# SparkFun_ZED-F9R_v12_uFL.net
KiCad netlist of a schematic drawn in EAGLE
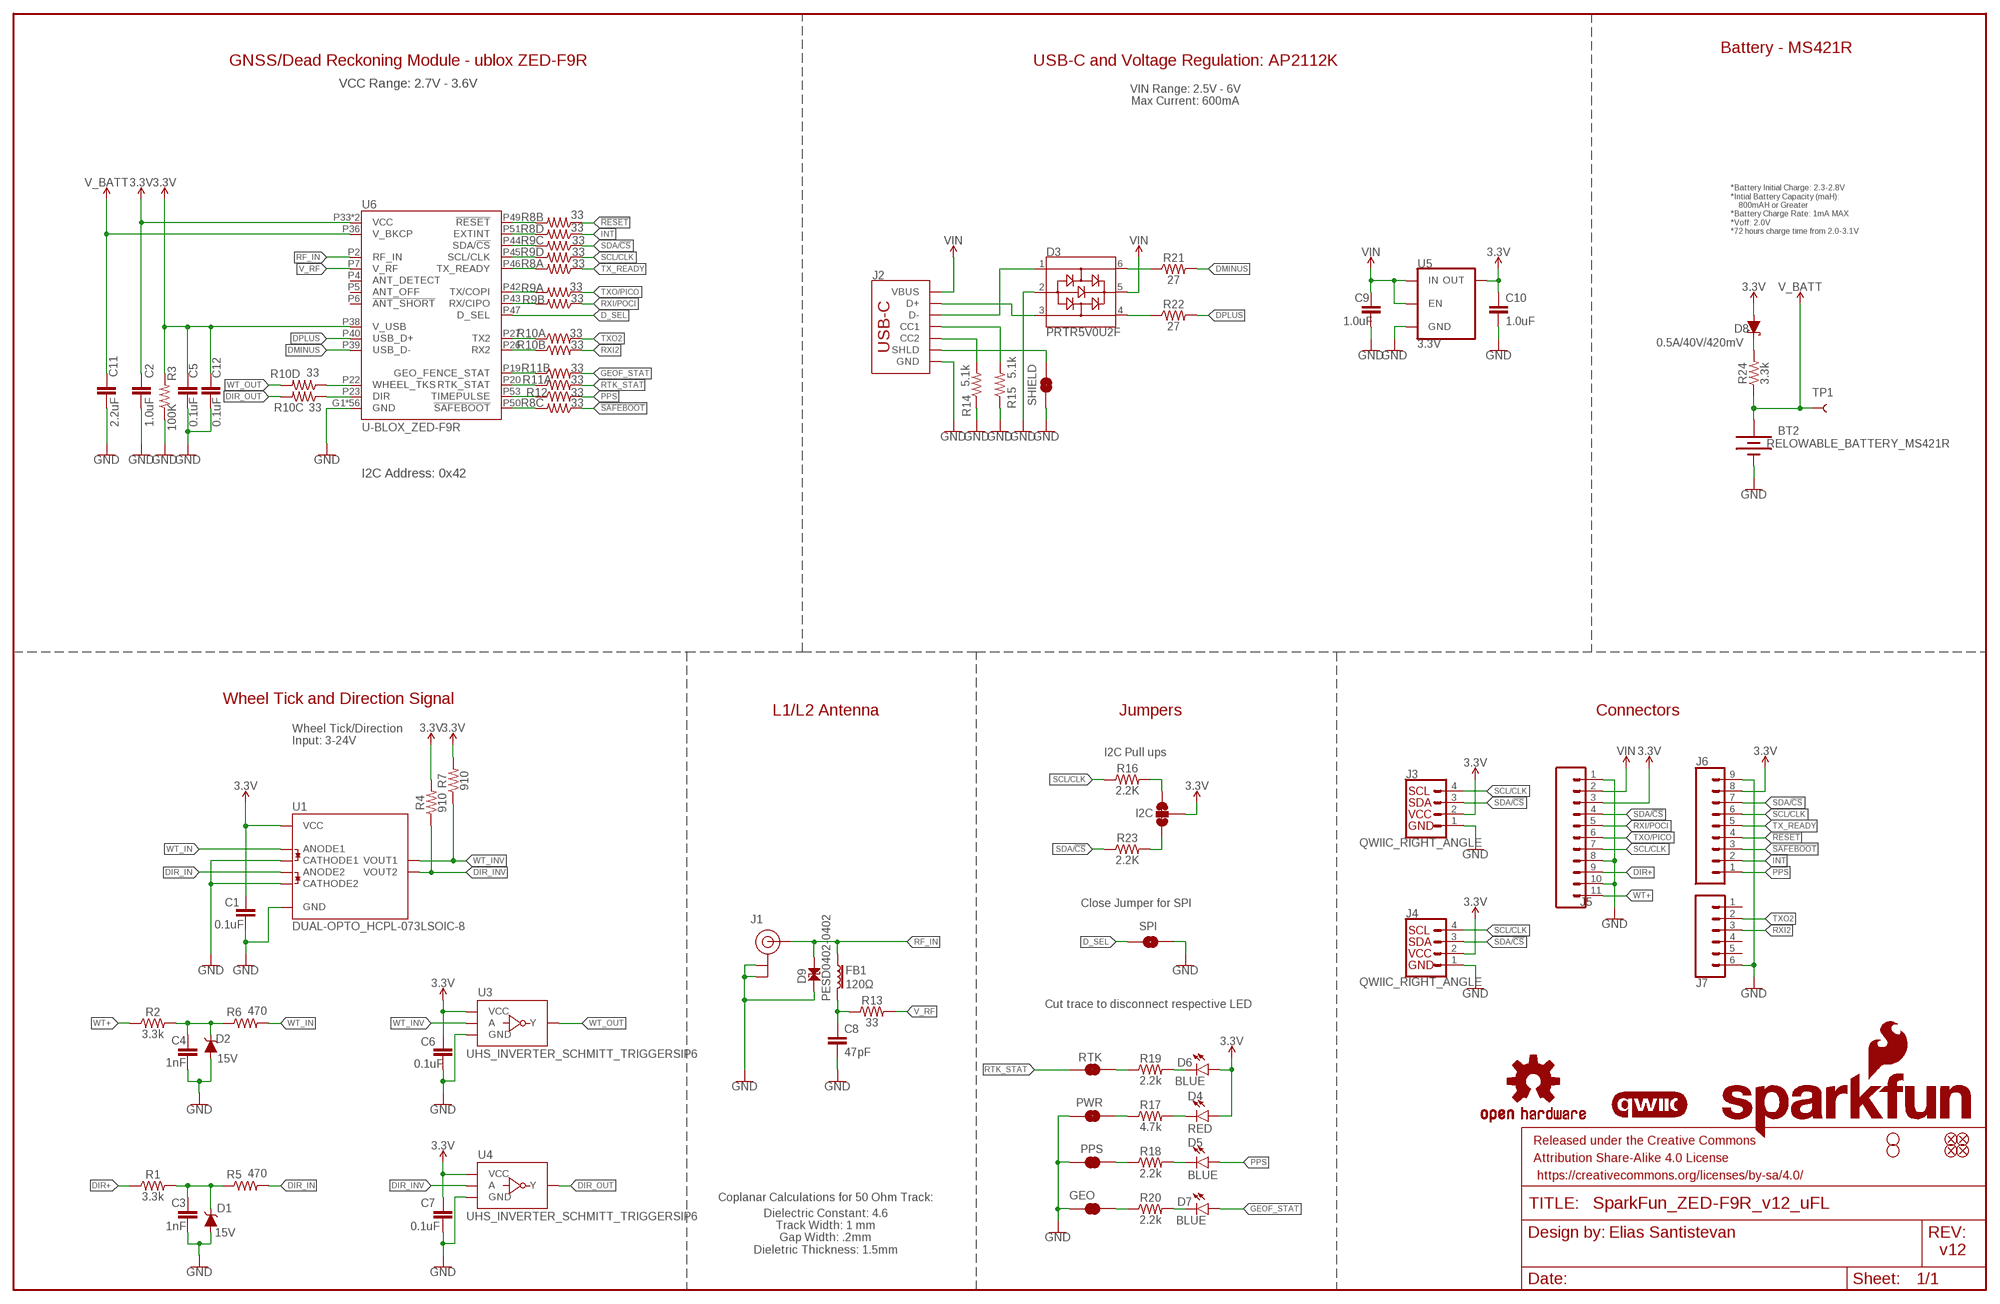
[diagram p0: schematic, sheet 1]

(export (version "E")
  (design (tool "Eeschema 10.0.6"))
  (components
    (comp (ref "$1_25_$_2020-03-30_22-52-05")
      (value "STAND-OFFTIGHT")
      (footprint "eagle-import:STAND-OFF-TIGHT")
      (libsource (lib "eagle-import") (part "STAND-OFFTIGHT"))
    )
    (comp (ref "BT2")
      (value "RELOWABLE_BATTERY_MS421R")
      (footprint "eagle-import:MS421R_IV03E")
      (libsource (lib "eagle-import") (part "RELOWABLE_BATTERY_MS421R"))
    )
    (comp (ref "C1")
      (value "0.1uF")
      (footprint "eagle-import:0402-TIGHT")
      (libsource (lib "eagle-import") (part "0.1UF-0402T-6.3V-10%-X7R"))
    )
    (comp (ref "C2")
      (value "1.0uF")
      (footprint "eagle-import:0402-TIGHT")
      (libsource (lib "eagle-import") (part "1.0UF-0402T-16V-10%"))
    )
    (comp (ref "C3")
      (value "1nF")
      (footprint "eagle-import:0402")
      (libsource (lib "eagle-import") (part "1.0NF/1000PF-0402-25V-10%-X7R"))
    )
    (comp (ref "C4")
      (value "1nF")
      (footprint "eagle-import:0402")
      (libsource (lib "eagle-import") (part "1.0NF/1000PF-0402-25V-10%-X7R"))
    )
    (comp (ref "C5")
      (value "0.1uF")
      (footprint "eagle-import:0402-TIGHT")
      (libsource (lib "eagle-import") (part "0.1UF-0402T-6.3V-10%-X7R"))
    )
    (comp (ref "C6")
      (value "0.1uF")
      (footprint "eagle-import:0402-TIGHT")
      (libsource (lib "eagle-import") (part "0.1UF-0402T-6.3V-10%-X7R"))
    )
    (comp (ref "C7")
      (value "0.1uF")
      (footprint "eagle-import:0402-TIGHT")
      (libsource (lib "eagle-import") (part "0.1UF-0402T-6.3V-10%-X7R"))
    )
    (comp (ref "C8")
      (value "47pF")
      (footprint "eagle-import:0402")
      (libsource (lib "eagle-import") (part "47PF-0402-25V-5%-X7R"))
    )
    (comp (ref "C9")
      (value "1.0uF")
      (footprint "eagle-import:0402-TIGHT")
      (libsource (lib "eagle-import") (part "1.0UF-0402T-16V-10%"))
    )
    (comp (ref "C10")
      (value "1.0uF")
      (footprint "eagle-import:0402-TIGHT")
      (libsource (lib "eagle-import") (part "1.0UF-0402T-16V-10%"))
    )
    (comp (ref "C11")
      (value "2.2uF")
      (footprint "eagle-import:0402-TIGHT")
      (libsource (lib "eagle-import") (part "2.2UF-0402_TIGHT-10V-10%-X5R"))
    )
    (comp (ref "C12")
      (value "0.1uF")
      (footprint "eagle-import:0402-TIGHT")
      (libsource (lib "eagle-import") (part "0.1UF-0402T-6.3V-10%-X7R"))
    )
    (comp (ref "D1")
      (value "15V")
      (footprint "eagle-import:SOT23-3")
      (libsource (lib "eagle-import") (part "DIODE-ZENER-BZX84C15LT3G"))
    )
    (comp (ref "D2")
      (value "15V")
      (footprint "eagle-import:SOT23-3")
      (libsource (lib "eagle-import") (part "DIODE-ZENER-BZX84C15LT3G"))
    )
    (comp (ref "D3")
      (value "PRTR5V0U2F")
      (footprint "eagle-import:SOT886")
      (libsource (lib "eagle-import") (part "PRTR5V0U2F"))
    )
    (comp (ref "D4")
      (value "RED")
      (footprint "eagle-import:LED-0603")
      (libsource (lib "eagle-import") (part "LED-RED_0603-KB"))
    )
    (comp (ref "D5")
      (value "BLUE")
      (footprint "eagle-import:LED-0603")
      (libsource (lib "eagle-import") (part "LED-BLUE0603"))
    )
    (comp (ref "D6")
      (value "BLUE")
      (footprint "eagle-import:LED-0603")
      (libsource (lib "eagle-import") (part "LED-BLUE0603"))
    )
    (comp (ref "D7")
      (value "BLUE")
      (footprint "eagle-import:LED-0603")
      (libsource (lib "eagle-import") (part "LED-BLUE0603"))
    )
    (comp (ref "D8")
      (value "0.5A/40V/420mV")
      (footprint "eagle-import:SOD-323")
      (libsource (lib "eagle-import") (part "DIODE-SCHOTTKY-PMEG4005EJ"))
    )
    (comp (ref "D9")
      (value "PESD0402-0402")
      (footprint "eagle-import:0402")
      (fields
        (field (name "DIGIKEY_PART") "PESD0402-140CT-ND")
        (field (name "MOUSE_PART") "650-PESD0402-140")
      )
      (libsource (lib "eagle-import") (part "PESD0402-0402"))
    )
    (comp (ref "FB1")
      (value "120Ω")
      (footprint "eagle-import:0402")
      (fields (field (name "MFG_PART") "BLM15HB121SN1D"))
      (libsource (lib "eagle-import") (part "FERRITE_BEAD-120_OHM-0402"))
    )
    (comp (ref "FD1")
      (value "FIDUCIALUFIDUCIAL")
      (footprint "eagle-import:FIDUCIAL-MICRO")
      (libsource (lib "eagle-import") (part "FIDUCIALUFIDUCIAL"))
    )
    (comp (ref "FD2")
      (value "FIDUCIALUFIDUCIAL")
      (footprint "eagle-import:FIDUCIAL-MICRO")
      (libsource (lib "eagle-import") (part "FIDUCIALUFIDUCIAL"))
    )
    (comp (ref "FD3")
      (value "FIDUCIALUFIDUCIAL")
      (footprint "eagle-import:FIDUCIAL-MICRO")
      (libsource (lib "eagle-import") (part "FIDUCIALUFIDUCIAL"))
    )
    (comp (ref "FD4")
      (value "FIDUCIALUFIDUCIAL")
      (footprint "eagle-import:FIDUCIAL-MICRO")
      (libsource (lib "eagle-import") (part "FIDUCIALUFIDUCIAL"))
    )
    (comp (ref "FRAME1")
      (value "FRAME-LEDGER")
      (footprint "eagle-import:CREATIVE_COMMONS")
      (libsource (lib "eagle-import") (part "FRAME-LEDGER"))
    )
    (comp (ref "GEO")
      (value "JUMPER-SMT_2_NC_TRACE_SILK")
      (footprint "eagle-import:SMT-JUMPER_2_NC_TRACE_SILK")
      (libsource (lib "eagle-import") (part "JUMPER-SMT_2_NC_TRACE_SILK"))
    )
    (comp (ref "H2")
      (value "STAND-OFFTIGHT")
      (footprint "eagle-import:STAND-OFF-TIGHT")
      (libsource (lib "eagle-import") (part "STAND-OFFTIGHT"))
    )
    (comp (ref "I2C")
      (value "JUMPER-SMT_3_2-NC_TRACE_SILK")
      (footprint "eagle-import:SMT-JUMPER_3_2-NC_TRACE_SILK")
      (libsource (lib "eagle-import") (part "JUMPER-SMT_3_2-NC_TRACE_SILK"))
    )
    (comp (ref "J1")
      (value "U.FL")
      (footprint "eagle-import:U.FL")
      (libsource (lib "eagle-import") (part "U.FL"))
    )
    (comp (ref "J2")
      (value "USB_C_2-LAYER_PADS")
      (footprint "eagle-import:USB-C-16P-2LAYER-PADS")
      (libsource (lib "eagle-import") (part "USB_C_2-LAYER_PADS"))
    )
    (comp (ref "J3")
      (value "QWIIC_RIGHT_ANGLE")
      (footprint "eagle-import:JST04_1MM_RA")
      (libsource (lib "eagle-import") (part "QWIIC_CONNECTORJS-1MM"))
    )
    (comp (ref "J4")
      (value "QWIIC_RIGHT_ANGLE")
      (footprint "eagle-import:JST04_1MM_RA")
      (libsource (lib "eagle-import") (part "QWIIC_CONNECTORJS-1MM"))
    )
    (comp (ref "J5")
      (value "CONN_111X11_NO_SILK")
      (footprint "eagle-import:1X11_NO_SILK")
      (libsource (lib "eagle-import") (part "CONN_111X11_NO_SILK"))
    )
    (comp (ref "J6")
      (value "CONN_09NO_SILK")
      (footprint "eagle-import:1X09_NO_SILK")
      (libsource (lib "eagle-import") (part "CONN_09NO_SILK"))
    )
    (comp (ref "J7")
      (value "CONN_06NO_SILK_NO_POP")
      (footprint "eagle-import:1X06_NO_SILK")
      (libsource (lib "eagle-import") (part "CONN_06NO_SILK_NO_POP"))
    )
    (comp (ref "LOGO1")
      (value "OSHW-LOGOS")
      (footprint "eagle-import:OSHW-LOGO-S")
      (libsource (lib "eagle-import") (part "OSHW-LOGOS"))
    )
    (comp (ref "LOGO2")
      (value "QWIIC_LOGO_4MM")
      (footprint "eagle-import:QWIIC_4MM")
      (libsource (lib "eagle-import") (part "QWIIC_LOGO_4MM"))
    )
    (comp (ref "LOGO3")
      (value "SFE_LOGO_NAME_FLAME.2_INCH")
      (footprint "eagle-import:SFE_LOGO_NAME_FLAME_.2")
      (libsource (lib "eagle-import") (part "SFE_LOGO_NAME_FLAME.2_INCH"))
    )
    (comp (ref "PPS")
      (value "JUMPER-SMT_2_NC_TRACE_SILK")
      (footprint "eagle-import:SMT-JUMPER_2_NC_TRACE_SILK")
      (libsource (lib "eagle-import") (part "JUMPER-SMT_2_NC_TRACE_SILK"))
    )
    (comp (ref "PWR")
      (value "JUMPER-SMT_2_NC_TRACE_SILK")
      (footprint "eagle-import:SMT-JUMPER_2_NC_TRACE_SILK")
      (libsource (lib "eagle-import") (part "JUMPER-SMT_2_NC_TRACE_SILK"))
    )
    (comp (ref "R1")
      (value "3.3k")
      (footprint "eagle-import:0603")
      (libsource (lib "eagle-import") (part "3.3KOHM-0603-1/10W-1%"))
    )
    (comp (ref "R2")
      (value "3.3k")
      (footprint "eagle-import:0603")
      (libsource (lib "eagle-import") (part "3.3KOHM-0603-1/10W-1%"))
    )
    (comp (ref "R3")
      (value "100K")
      (footprint "eagle-import:0402")
      (libsource (lib "eagle-import") (part "100KOHM-0402-1/16W-1%"))
    )
    (comp (ref "R4")
      (value "910")
      (footprint "eagle-import:0603")
      (libsource (lib "eagle-import") (part "910OHM-0603-1/10W-5%"))
    )
    (comp (ref "R5")
      (value "470")
      (footprint "eagle-import:0603")
      (libsource (lib "eagle-import") (part "470OHM-0603-1/10W-1%"))
    )
    (comp (ref "R6")
      (value "470")
      (footprint "eagle-import:0603")
      (libsource (lib "eagle-import") (part "470OHM-0603-1/10W-1%"))
    )
    (comp (ref "R7")
      (value "910")
      (footprint "eagle-import:0603")
      (libsource (lib "eagle-import") (part "910OHM-0603-1/10W-5%"))
    )
    (comp (ref "R8")
      (value "33")
      (footprint "eagle-import:1206_RA")
      (libsource (lib "eagle-import") (part "33OHM_RA-1206-1/16W-5%"))
    )
    (comp (ref "R9")
      (value "33")
      (footprint "eagle-import:1206_RA")
      (libsource (lib "eagle-import") (part "33OHM_RA-1206-1/16W-5%"))
    )
    (comp (ref "R10")
      (value "33")
      (footprint "eagle-import:1206_RA")
      (libsource (lib "eagle-import") (part "33OHM_RA-1206-1/16W-5%"))
    )
    (comp (ref "R11")
      (value "33")
      (footprint "eagle-import:1206_RA")
      (libsource (lib "eagle-import") (part "33OHM_RA-1206-1/16W-5%"))
    )
    (comp (ref "R12")
      (value "33")
      (footprint "eagle-import:0603")
      (libsource (lib "eagle-import") (part "33OHM-0603-1/10W-1%"))
    )
    (comp (ref "R13")
      (value "33")
      (footprint "eagle-import:0603")
      (libsource (lib "eagle-import") (part "33OHM-0603-1/10W-1%"))
    )
    (comp (ref "R14")
      (value "5.1k")
      (footprint "eagle-import:0402")
      (libsource (lib "eagle-import") (part "5.1KOHM-0402-1/16W-1%"))
    )
    (comp (ref "R15")
      (value "5.1k")
      (footprint "eagle-import:0402")
      (libsource (lib "eagle-import") (part "5.1KOHM-0402-1/16W-1%"))
    )
    (comp (ref "R16")
      (value "2.2K")
      (footprint "eagle-import:0402")
      (libsource (lib "eagle-import") (part "2.2KOHM-0402-1/16W-1%"))
    )
    (comp (ref "R17")
      (value "4.7k")
      (footprint "eagle-import:0603")
      (libsource (lib "eagle-import") (part "4.7KOHM-0603-1/10W-1%"))
    )
    (comp (ref "R18")
      (value "2.2k")
      (footprint "eagle-import:0603")
      (libsource (lib "eagle-import") (part "2.2KOHM-0603-1/10W-1%"))
    )
    (comp (ref "R19")
      (value "2.2k")
      (footprint "eagle-import:0603")
      (libsource (lib "eagle-import") (part "2.2KOHM-0603-1/10W-1%"))
    )
    (comp (ref "R20")
      (value "2.2k")
      (footprint "eagle-import:0603")
      (libsource (lib "eagle-import") (part "2.2KOHM-0603-1/10W-1%"))
    )
    (comp (ref "R21")
      (value "27")
      (footprint "eagle-import:0603")
      (libsource (lib "eagle-import") (part "27OHM-0603-1/10W-1%"))
    )
    (comp (ref "R22")
      (value "27")
      (footprint "eagle-import:0603")
      (libsource (lib "eagle-import") (part "27OHM-0603-1/10W-1%"))
    )
    (comp (ref "R23")
      (value "2.2K")
      (footprint "eagle-import:0402")
      (libsource (lib "eagle-import") (part "2.2KOHM-0402-1/16W-1%"))
    )
    (comp (ref "R24")
      (value "3.3k")
      (footprint "eagle-import:0603")
      (libsource (lib "eagle-import") (part "3.3KOHM-0603-1/10W-1%"))
    )
    (comp (ref "RTK")
      (value "JUMPER-SMT_2_NC_TRACE_SILK")
      (footprint "eagle-import:SMT-JUMPER_2_NC_TRACE_SILK")
      (libsource (lib "eagle-import") (part "JUMPER-SMT_2_NC_TRACE_SILK"))
    )
    (comp (ref "SHIELD")
      (value "JUMPER-SMT_2_NC_TRACE_SILK")
      (footprint "eagle-import:SMT-JUMPER_2_NC_TRACE_SILK")
      (libsource (lib "eagle-import") (part "JUMPER-SMT_2_NC_TRACE_SILK"))
    )
    (comp (ref "SPI")
      (value "JUMPER-SMT_2_NO_SILK")
      (footprint "eagle-import:SMT-JUMPER_2_NO_SILK")
      (libsource (lib "eagle-import") (part "JUMPER-SMT_2_NO_SILK"))
    )
    (comp (ref "TP1")
      (value "TEST-POINT3X5")
      (footprint "eagle-import:PAD.03X.05")
      (libsource (lib "eagle-import") (part "TEST-POINT3X5"))
    )
    (comp (ref "U1")
      (value "DUAL-OPTO_HCPL-073LSOIC-8")
      (footprint "eagle-import:SO08")
      (libsource (lib "eagle-import") (part "DUAL-OPTO_HCPL-073LSOIC-8"))
    )
    (comp (ref "U3")
      (value "UHS_INVERTER_SCHMITT_TRIGGERSIP6")
      (footprint "eagle-import:SIP6_MICROPAK2")
      (libsource (lib "eagle-import") (part "UHS_INVERTER_SCHMITT_TRIGGER_MPAK2"))
    )
    (comp (ref "U4")
      (value "UHS_INVERTER_SCHMITT_TRIGGERSIP6")
      (footprint "eagle-import:SIP6_MICROPAK2")
      (libsource (lib "eagle-import") (part "UHS_INVERTER_SCHMITT_TRIGGER_MPAK2"))
    )
    (comp (ref "U5")
      (value "3.3V")
      (footprint "eagle-import:SOT23-5")
      (libsource (lib "eagle-import") (part "V_REG_AP2112K-3.3V"))
    )
    (comp (ref "U6")
      (value "U-BLOX_ZED-F9R")
      (footprint "eagle-import:UBLOX_ZED_F9R")
      (libsource (lib "eagle-import") (part "U-BLOX_ZED-F9R"))
    )
  )
  (nets
    (net (code "1") (name "/SDA{slash}~{CS}") (class "Default")
      (node (ref "J3") (pin "3") (pinfunction "3_3") (pintype "passive"))
      (node (ref "J4") (pin "3") (pinfunction "3_3") (pintype "passive"))
      (node (ref "J5") (pin "4") (pinfunction "4_4") (pintype "passive"))
      (node (ref "J6") (pin "7") (pinfunction "7_7") (pintype "passive"))
      (node (ref "R23") (pin "1") (pinfunction "1_1") (pintype "passive"))
      (node (ref "R9") (pin "P3") (pinfunction "1_P3") (pintype "passive"))
    )
    (net (code "2") (name "/~{RESET}") (class "Default")
      (node (ref "J6") (pin "4") (pinfunction "4_4") (pintype "passive"))
      (node (ref "R8") (pin "P2") (pinfunction "1_P2") (pintype "passive"))
    )
    (net (code "3") (name "/~{SAFEBOOT}") (class "Default")
      (node (ref "J6") (pin "3") (pinfunction "3_3") (pintype "passive"))
      (node (ref "R8") (pin "P3") (pinfunction "1_P3") (pintype "passive"))
    )
    (net (code "4") (name "3.3V") (class "Default")
      (node (ref "C1") (pin "1") (pinfunction "1_1") (pintype "passive"))
      (node (ref "C10") (pin "1") (pinfunction "1_1") (pintype "passive"))
      (node (ref "C12") (pin "1") (pinfunction "1_1") (pintype "passive"))
      (node (ref "C2") (pin "1") (pinfunction "1_1") (pintype "passive"))
      (node (ref "C5") (pin "1") (pinfunction "1_1") (pintype "passive"))
      (node (ref "C6") (pin "1") (pinfunction "1_1") (pintype "passive"))
      (node (ref "C7") (pin "1") (pinfunction "1_1") (pintype "passive"))
      (node (ref "D4") (pin "A") (pinfunction "A_A") (pintype "passive"))
      (node (ref "D6") (pin "A") (pinfunction "A_A") (pintype "passive"))
      (node (ref "D8") (pin "A") (pinfunction "A_A") (pintype "passive"))
      (node (ref "I2C") (pin "2") (pinfunction "2_2") (pintype "passive"))
      (node (ref "J3") (pin "2") (pinfunction "2_2") (pintype "power_in"))
      (node (ref "J4") (pin "2") (pinfunction "2_2") (pintype "power_in"))
      (node (ref "J5") (pin "3") (pinfunction "3_3") (pintype "passive"))
      (node (ref "J6") (pin "8") (pinfunction "8_8") (pintype "passive"))
      (node (ref "R3") (pin "2") (pinfunction "2_2") (pintype "passive"))
      (node (ref "R4") (pin "2") (pinfunction "2_2") (pintype "passive"))
      (node (ref "R7") (pin "2") (pinfunction "2_2") (pintype "passive"))
      (node (ref "U1") (pin "8") (pinfunction "VCC_8") (pintype "power_in"))
      (node (ref "U3") (pin "P6") (pinfunction "VCC_P6") (pintype "power_in"))
      (node (ref "U4") (pin "P6") (pinfunction "VCC_P6") (pintype "power_in"))
      (node (ref "U5") (pin "5") (pinfunction "OUT_5") (pintype "passive"))
      (node (ref "U6") (pin "P33") (pinfunction "VCC_P33") (pintype "power_in"))
      (node (ref "U6") (pin "P34") (pinfunction "VCC_P34") (pintype "power_in"))
      (node (ref "U6") (pin "P38") (pinfunction "V_USB_P38") (pintype "power_in"))
    )
    (net (code "5") (name "DIR+") (class "Default")
      (node (ref "J5") (pin "9") (pinfunction "9_9") (pintype "passive"))
      (node (ref "R1") (pin "1") (pinfunction "1_1") (pintype "passive"))
    )
    (net (code "6") (name "DIR_IN") (class "Default")
      (node (ref "R5") (pin "2") (pinfunction "2_2") (pintype "passive"))
      (node (ref "U1") (pin "4") (pinfunction "ANODE2_4") (pintype "input"))
    )
    (net (code "7") (name "DIR_INV") (class "Default")
      (node (ref "R4") (pin "1") (pinfunction "1_1") (pintype "passive"))
      (node (ref "U1") (pin "6") (pinfunction "VOUT2_6") (pintype "output"))
      (node (ref "U4") (pin "P2") (pinfunction "A_P2") (pintype "input"))
    )
    (net (code "8") (name "DIR_OUT") (class "Default")
      (node (ref "R10") (pin "P6") (pinfunction "2_P6") (pintype "passive"))
      (node (ref "U4") (pin "P4") (pinfunction "Y_P4") (pintype "output"))
    )
    (net (code "9") (name "DMINUS") (class "Default")
      (node (ref "R21") (pin "2") (pinfunction "2_2") (pintype "passive"))
      (node (ref "U6") (pin "P39") (pinfunction "USB_D-_P39") (pintype "bidirectional"))
    )
    (net (code "10") (name "DPLUS") (class "Default")
      (node (ref "R22") (pin "2") (pinfunction "2_2") (pintype "passive"))
      (node (ref "U6") (pin "P40") (pinfunction "USB_D+_P40") (pintype "bidirectional"))
    )
    (net (code "11") (name "D_SEL") (class "Default")
      (node (ref "SPI") (pin "1") (pinfunction "1_1") (pintype "passive"))
      (node (ref "U6") (pin "P47") (pinfunction "D_SEL_P47") (pintype "bidirectional"))
    )
    (net (code "12") (name "GEOF_STAT") (class "Default")
      (node (ref "D7") (pin "A") (pinfunction "A_A") (pintype "passive"))
      (node (ref "R11") (pin "P7") (pinfunction "2_P7") (pintype "passive"))
    )
    (net (code "13") (name "GND") (class "Default")
      (node (ref "BT2") (pin "-") (pinfunction "-_-") (pintype "power_in"))
      (node (ref "C1") (pin "2") (pinfunction "2_2") (pintype "passive"))
      (node (ref "C10") (pin "2") (pinfunction "2_2") (pintype "passive"))
      (node (ref "C11") (pin "2") (pinfunction "2_2") (pintype "passive"))
      (node (ref "C12") (pin "2") (pinfunction "2_2") (pintype "passive"))
      (node (ref "C2") (pin "2") (pinfunction "2_2") (pintype "passive"))
      (node (ref "C3") (pin "2") (pinfunction "2_2") (pintype "passive"))
      (node (ref "C4") (pin "2") (pinfunction "2_2") (pintype "passive"))
      (node (ref "C5") (pin "2") (pinfunction "2_2") (pintype "passive"))
      (node (ref "C6") (pin "2") (pinfunction "2_2") (pintype "passive"))
      (node (ref "C7") (pin "2") (pinfunction "2_2") (pintype "passive"))
      (node (ref "C8") (pin "2") (pinfunction "2_2") (pintype "passive"))
      (node (ref "C9") (pin "2") (pinfunction "2_2") (pintype "passive"))
      (node (ref "D1") (pin "1") (pinfunction "A_1") (pintype "passive"))
      (node (ref "D2") (pin "1") (pinfunction "A_1") (pintype "passive"))
      (node (ref "D3") (pin "2") (pinfunction "2_2") (pintype "power_in"))
      (node (ref "D9") (pin "1") (pinfunction "1_1") (pintype "bidirectional"))
      (node (ref "GEO") (pin "1") (pinfunction "1_1") (pintype "passive"))
      (node (ref "J1") (pin "1") (pinfunction "GND_1") (pintype "bidirectional"))
      (node (ref "J1") (pin "2") (pinfunction "GND_2") (pintype "bidirectional"))
      (node (ref "J2") (pin "GND") (pinfunction "GND_GND") (pintype "bidirectional"))
      (node (ref "J2") (pin "GND2") (pinfunction "GND_GND2") (pintype "bidirectional"))
      (node (ref "J3") (pin "1") (pinfunction "1_1") (pintype "power_in"))
      (node (ref "J4") (pin "1") (pinfunction "1_1") (pintype "power_in"))
      (node (ref "J5") (pin "1") (pinfunction "1_1") (pintype "passive"))
      (node (ref "J5") (pin "10") (pinfunction "10_10") (pintype "passive"))
      (node (ref "J5") (pin "8") (pinfunction "8_8") (pintype "passive"))
      (node (ref "J6") (pin "9") (pinfunction "9_9") (pintype "passive"))
      (node (ref "J7") (pin "6") (pinfunction "6_6") (pintype "passive"))
      (node (ref "PPS") (pin "1") (pinfunction "1_1") (pintype "passive"))
      (node (ref "PWR") (pin "1") (pinfunction "1_1") (pintype "passive"))
      (node (ref "R14") (pin "1") (pinfunction "1_1") (pintype "passive"))
      (node (ref "R15") (pin "1") (pinfunction "1_1") (pintype "passive"))
      (node (ref "R3") (pin "1") (pinfunction "1_1") (pintype "passive"))
      (node (ref "SHIELD") (pin "1") (pinfunction "1_1") (pintype "passive"))
      (node (ref "SPI") (pin "2") (pinfunction "2_2") (pintype "passive"))
      (node (ref "U1") (pin "2") (pinfunction "CATHODE1_2") (pintype "input"))
      (node (ref "U1") (pin "3") (pinfunction "CATHODE2_3") (pintype "input"))
      (node (ref "U1") (pin "5") (pinfunction "GND_5") (pintype "power_in"))
      (node (ref "U3") (pin "P3") (pinfunction "GND_P3") (pintype "power_in"))
      (node (ref "U4") (pin "P3") (pinfunction "GND_P3") (pintype "power_in"))
      (node (ref "U5") (pin "2") (pinfunction "GND_2") (pintype "input"))
      (node (ref "U6") (pin "G1") (pinfunction "GND_G1") (pintype "power_in"))
      (node (ref "U6") (pin "G10") (pinfunction "GND_G10") (pintype "power_in"))
      (node (ref "U6") (pin "G11") (pinfunction "GND_G11") (pintype "power_in"))
      (node (ref "U6") (pin "G12") (pinfunction "GND_G12") (pintype "power_in"))
      (node (ref "U6") (pin "G13") (pinfunction "GND_G13") (pintype "power_in"))
      (node (ref "U6") (pin "G14") (pinfunction "GND_G14") (pintype "power_in"))
      (node (ref "U6") (pin "G15") (pinfunction "GND_G15") (pintype "power_in"))
      (node (ref "U6") (pin "G16") (pinfunction "GND_G16") (pintype "power_in"))
      (node (ref "U6") (pin "G17") (pinfunction "GND_G17") (pintype "power_in"))
      (node (ref "U6") (pin "G18") (pinfunction "GND_G18") (pintype "power_in"))
      (node (ref "U6") (pin "G19") (pinfunction "GND_G19") (pintype "power_in"))
      (node (ref "U6") (pin "G2") (pinfunction "GND_G2") (pintype "power_in"))
      (node (ref "U6") (pin "G20") (pinfunction "GND_G20") (pintype "power_in"))
      (node (ref "U6") (pin "G21") (pinfunction "GND_G21") (pintype "power_in"))
      (node (ref "U6") (pin "G22") (pinfunction "GND_G22") (pintype "power_in"))
      (node (ref "U6") (pin "G23") (pinfunction "GND_G23") (pintype "power_in"))
      (node (ref "U6") (pin "G24") (pinfunction "GND_G24") (pintype "power_in"))
      (node (ref "U6") (pin "G25") (pinfunction "GND_G25") (pintype "power_in"))
      (node (ref "U6") (pin "G26") (pinfunction "GND_G26") (pintype "power_in"))
      (node (ref "U6") (pin "G27") (pinfunction "GND_G27") (pintype "power_in"))
      (node (ref "U6") (pin "G28") (pinfunction "GND_G28") (pintype "power_in"))
      (node (ref "U6") (pin "G29") (pinfunction "GND_G29") (pintype "power_in"))
      (node (ref "U6") (pin "G3") (pinfunction "GND_G3") (pintype "power_in"))
      (node (ref "U6") (pin "G30") (pinfunction "GND_G30") (pintype "power_in"))
      (node (ref "U6") (pin "G31") (pinfunction "GND_G31") (pintype "power_in"))
      (node (ref "U6") (pin "G32") (pinfunction "GND_G32") (pintype "power_in"))
      (node (ref "U6") (pin "G33") (pinfunction "GND_G33") (pintype "power_in"))
      (node (ref "U6") (pin "G34") (pinfunction "GND_G34") (pintype "power_in"))
      (node (ref "U6") (pin "G35") (pinfunction "GND_G35") (pintype "power_in"))
      (node (ref "U6") (pin "G36") (pinfunction "GND_G36") (pintype "power_in"))
      (node (ref "U6") (pin "G37") (pinfunction "GND_G37") (pintype "power_in"))
      (node (ref "U6") (pin "G38") (pinfunction "GND_G38") (pintype "power_in"))
      (node (ref "U6") (pin "G39") (pinfunction "GND_G39") (pintype "power_in"))
      (node (ref "U6") (pin "G4") (pinfunction "GND_G4") (pintype "power_in"))
      (node (ref "U6") (pin "G40") (pinfunction "GND_G40") (pintype "power_in"))
      (node (ref "U6") (pin "G41") (pinfunction "GND_G41") (pintype "power_in"))
      (node (ref "U6") (pin "G42") (pinfunction "GND_G42") (pintype "power_in"))
      (node (ref "U6") (pin "G43") (pinfunction "GND_G43") (pintype "power_in"))
      (node (ref "U6") (pin "G44") (pinfunction "GND_G44") (pintype "power_in"))
      (node (ref "U6") (pin "G45") (pinfunction "GND_G45") (pintype "power_in"))
      (node (ref "U6") (pin "G46") (pinfunction "GND_G46") (pintype "power_in"))
      (node (ref "U6") (pin "G47") (pinfunction "GND_G47") (pintype "power_in"))
      (node (ref "U6") (pin "G48") (pinfunction "GND_G48") (pintype "power_in"))
      (node (ref "U6") (pin "G5") (pinfunction "GND_G5") (pintype "power_in"))
      (node (ref "U6") (pin "G6") (pinfunction "GND_G6") (pintype "power_in"))
      (node (ref "U6") (pin "G7") (pinfunction "GND_G7") (pintype "power_in"))
      (node (ref "U6") (pin "G8") (pinfunction "GND_G8") (pintype "power_in"))
      (node (ref "U6") (pin "G9") (pinfunction "GND_G9") (pintype "power_in"))
      (node (ref "U6") (pin "P1") (pinfunction "GND_P1") (pintype "power_in"))
      (node (ref "U6") (pin "P12") (pinfunction "GND_P12") (pintype "power_in"))
      (node (ref "U6") (pin "P14") (pinfunction "GND_P14") (pintype "power_in"))
      (node (ref "U6") (pin "P3") (pinfunction "GND_P3") (pintype "power_in"))
      (node (ref "U6") (pin "P32") (pinfunction "GND_P32") (pintype "power_in"))
      (node (ref "U6") (pin "P37") (pinfunction "GND_P37") (pintype "power_in"))
      (node (ref "U6") (pin "P41") (pinfunction "GND_P41") (pintype "power_in"))
      (node (ref "U6") (pin "P48") (pinfunction "GND_P48") (pintype "power_in"))
    )
    (net (code "14") (name "INT") (class "Default")
      (node (ref "J6") (pin "2") (pinfunction "2_2") (pintype "passive"))
      (node (ref "R8") (pin "P4") (pinfunction "1_P4") (pintype "passive"))
    )
    (net (code "15") (name "Net-(C8-Pad1)") (class "Default")
      (node (ref "C8") (pin "1") (pinfunction "1_1") (pintype "passive"))
      (node (ref "FB1") (pin "2") (pinfunction "2_2") (pintype "passive"))
      (node (ref "R13") (pin "1") (pinfunction "1_1") (pintype "passive"))
    )
    (net (code "16") (name "Net-(D1-C)") (class "Default")
      (node (ref "C3") (pin "1") (pinfunction "1_1") (pintype "passive"))
      (node (ref "D1") (pin "3") (pinfunction "C_3") (pintype "passive"))
      (node (ref "R1") (pin "2") (pinfunction "2_2") (pintype "passive"))
      (node (ref "R5") (pin "1") (pinfunction "1_1") (pintype "passive"))
    )
    (net (code "17") (name "Net-(D2-C)") (class "Default")
      (node (ref "C4") (pin "1") (pinfunction "1_1") (pintype "passive"))
      (node (ref "D2") (pin "3") (pinfunction "C_3") (pintype "passive"))
      (node (ref "R2") (pin "2") (pinfunction "2_2") (pintype "passive"))
      (node (ref "R6") (pin "1") (pinfunction "1_1") (pintype "passive"))
    )
    (net (code "18") (name "Net-(D3-Pad1)") (class "Default")
      (node (ref "D3") (pin "1") (pinfunction "1_1") (pintype "bidirectional"))
      (node (ref "J2") (pin "A7") (pinfunction "D-_A7") (pintype "bidirectional"))
      (node (ref "J2") (pin "B7") (pinfunction "D-_B7") (pintype "bidirectional"))
    )
    (net (code "19") (name "Net-(D3-Pad3)") (class "Default")
      (node (ref "D3") (pin "3") (pinfunction "3_3") (pintype "bidirectional"))
      (node (ref "J2") (pin "A6") (pinfunction "D+_A6") (pintype "bidirectional"))
      (node (ref "J2") (pin "B6") (pinfunction "D+_B6") (pintype "bidirectional"))
    )
    (net (code "20") (name "Net-(D3-Pad4)") (class "Default")
      (node (ref "D3") (pin "4") (pinfunction "4_4") (pintype "bidirectional"))
      (node (ref "R22") (pin "1") (pinfunction "1_1") (pintype "passive"))
    )
    (net (code "21") (name "Net-(D3-Pad6)") (class "Default")
      (node (ref "D3") (pin "6") (pinfunction "6_6") (pintype "bidirectional"))
      (node (ref "R21") (pin "1") (pinfunction "1_1") (pintype "passive"))
    )
    (net (code "22") (name "Net-(D4-PadC)") (class "Default")
      (node (ref "D4") (pin "C") (pinfunction "C_C") (pintype "passive"))
      (node (ref "R17") (pin "2") (pinfunction "2_2") (pintype "passive"))
    )
    (net (code "23") (name "Net-(D5-PadC)") (class "Default")
      (node (ref "D5") (pin "C") (pinfunction "C_C") (pintype "passive"))
      (node (ref "R18") (pin "2") (pinfunction "2_2") (pintype "passive"))
    )
    (net (code "24") (name "Net-(D6-PadC)") (class "Default")
      (node (ref "D6") (pin "C") (pinfunction "C_C") (pintype "passive"))
      (node (ref "R19") (pin "2") (pinfunction "2_2") (pintype "passive"))
    )
    (net (code "25") (name "Net-(D7-PadC)") (class "Default")
      (node (ref "D7") (pin "C") (pinfunction "C_C") (pintype "passive"))
      (node (ref "R20") (pin "2") (pinfunction "2_2") (pintype "passive"))
    )
    (net (code "26") (name "Net-(D8-PadC)") (class "Default")
      (node (ref "D8") (pin "C") (pinfunction "C_C") (pintype "passive"))
      (node (ref "R24") (pin "2") (pinfunction "2_2") (pintype "passive"))
    )
    (net (code "27") (name "Net-(GEO-Pad2)") (class "Default")
      (node (ref "GEO") (pin "2") (pinfunction "2_2") (pintype "passive"))
      (node (ref "R20") (pin "1") (pinfunction "1_1") (pintype "passive"))
    )
    (net (code "28") (name "Net-(I2C-Pad1)") (class "Default")
      (node (ref "I2C") (pin "1") (pinfunction "1_1") (pintype "passive"))
      (node (ref "R23") (pin "2") (pinfunction "2_2") (pintype "passive"))
    )
    (net (code "29") (name "Net-(I2C-Pad3)") (class "Default")
      (node (ref "I2C") (pin "3") (pinfunction "3_3") (pintype "passive"))
      (node (ref "R16") (pin "2") (pinfunction "2_2") (pintype "passive"))
    )
    (net (code "30") (name "Net-(J2-CC1)") (class "Default")
      (node (ref "J2") (pin "A5") (pinfunction "CC1_A5") (pintype "bidirectional"))
      (node (ref "R15") (pin "2") (pinfunction "2_2") (pintype "passive"))
    )
    (net (code "31") (name "Net-(J2-CC2)") (class "Default")
      (node (ref "J2") (pin "B5") (pinfunction "CC2_B5") (pintype "bidirectional"))
      (node (ref "R14") (pin "2") (pinfunction "2_2") (pintype "passive"))
    )
    (net (code "32") (name "Net-(J2-SHLD-PadSHLD1)") (class "Default")
      (node (ref "J2") (pin "SHLD1") (pinfunction "SHLD_SHLD1") (pintype "bidirectional"))
      (node (ref "J2") (pin "SHLD2") (pinfunction "SHLD_SHLD2") (pintype "bidirectional"))
      (node (ref "J2") (pin "SHLD3") (pinfunction "SHLD_SHLD3") (pintype "bidirectional"))
      (node (ref "J2") (pin "SHLD4") (pinfunction "SHLD_SHLD4") (pintype "bidirectional"))
      (node (ref "SHIELD") (pin "2") (pinfunction "2_2") (pintype "passive"))
    )
    (net (code "33") (name "Net-(PPS-Pad2)") (class "Default")
      (node (ref "PPS") (pin "2") (pinfunction "2_2") (pintype "passive"))
      (node (ref "R18") (pin "1") (pinfunction "1_1") (pintype "passive"))
    )
    (net (code "34") (name "Net-(PWR-Pad2)") (class "Default")
      (node (ref "PWR") (pin "2") (pinfunction "2_2") (pintype "passive"))
      (node (ref "R17") (pin "1") (pinfunction "1_1") (pintype "passive"))
    )
    (net (code "35") (name "Net-(R8A-2)") (class "Default")
      (node (ref "R8") (pin "P8") (pinfunction "2_P8") (pintype "passive"))
      (node (ref "U6") (pin "P46") (pinfunction "TX_READY_P46") (pintype "bidirectional"))
    )
    (net (code "36") (name "Net-(R8B-2)") (class "Default")
      (node (ref "R8") (pin "P7") (pinfunction "2_P7") (pintype "passive"))
      (node (ref "U6") (pin "P49") (pinfunction "~{RESET}_P49") (pintype "bidirectional"))
    )
    (net (code "37") (name "Net-(R8C-2)") (class "Default")
      (node (ref "R8") (pin "P6") (pinfunction "2_P6") (pintype "passive"))
      (node (ref "U6") (pin "P50") (pinfunction "~{SAFEBOOT}_P50") (pintype "input"))
    )
    (net (code "38") (name "Net-(R8D-2)") (class "Default")
      (node (ref "R8") (pin "P5") (pinfunction "2_P5") (pintype "passive"))
      (node (ref "U6") (pin "P51") (pinfunction "EXTINT_P51") (pintype "bidirectional"))
    )
    (net (code "39") (name "Net-(R9A-2)") (class "Default")
      (node (ref "R9") (pin "P8") (pinfunction "2_P8") (pintype "passive"))
      (node (ref "U6") (pin "P42") (pinfunction "TX/COPI_P42") (pintype "bidirectional"))
    )
    (net (code "40") (name "Net-(R9B-2)") (class "Default")
      (node (ref "R9") (pin "P7") (pinfunction "2_P7") (pintype "passive"))
      (node (ref "U6") (pin "P43") (pinfunction "RX/CIPO_P43") (pintype "bidirectional"))
    )
    (net (code "41") (name "Net-(R9C-2)") (class "Default")
      (node (ref "R9") (pin "P6") (pinfunction "2_P6") (pintype "passive"))
      (node (ref "U6") (pin "P44") (pinfunction "SDA/~{CS}_P44") (pintype "bidirectional"))
    )
    (net (code "42") (name "Net-(R9D-2)") (class "Default")
      (node (ref "R9") (pin "P5") (pinfunction "2_P5") (pintype "passive"))
      (node (ref "U6") (pin "P45") (pinfunction "SCL/CLK_P45") (pintype "bidirectional"))
    )
    (net (code "43") (name "Net-(R10A-1)") (class "Default")
      (node (ref "R10") (pin "P1") (pinfunction "1_P1") (pintype "passive"))
      (node (ref "U6") (pin "P27") (pinfunction "TX2_P27") (pintype "output"))
    )
    (net (code "44") (name "Net-(R10B-1)") (class "Default")
      (node (ref "R10") (pin "P2") (pinfunction "1_P2") (pintype "passive"))
      (node (ref "U6") (pin "P26") (pinfunction "RX2_P26") (pintype "input"))
    )
    (net (code "45") (name "Net-(R10C-1)") (class "Default")
      (node (ref "R10") (pin "P3") (pinfunction "1_P3") (pintype "passive"))
      (node (ref "U6") (pin "P23") (pinfunction "DIR_P23") (pintype "input"))
    )
    (net (code "46") (name "Net-(R10D-1)") (class "Default")
      (node (ref "R10") (pin "P4") (pinfunction "1_P4") (pintype "passive"))
      (node (ref "U6") (pin "P22") (pinfunction "WHEEL_TKS_P22") (pintype "input"))
    )
    (net (code "47") (name "Net-(R11A-1)") (class "Default")
      (node (ref "R11") (pin "P1") (pinfunction "1_P1") (pintype "passive"))
      (node (ref "U6") (pin "P20") (pinfunction "RTK_STAT_P20") (pintype "output"))
    )
    (net (code "48") (name "Net-(R11B-1)") (class "Default")
      (node (ref "R11") (pin "P2") (pinfunction "1_P2") (pintype "passive"))
      (node (ref "U6") (pin "P19") (pinfunction "GEO_FENCE_STAT_P19") (pintype "output"))
    )
    (net (code "49") (name "Net-(R19-Pad1)") (class "Default")
      (node (ref "R19") (pin "1") (pinfunction "1_1") (pintype "passive"))
      (node (ref "RTK") (pin "2") (pinfunction "2_2") (pintype "passive"))
    )
    (net (code "50") (name "Net-(U6-TIMEPULSE)") (class "Default")
      (node (ref "R12") (pin "1") (pinfunction "1_1") (pintype "passive"))
      (node (ref "U6") (pin "P53") (pinfunction "TIMEPULSE_P53") (pintype "output"))
    )
    (net (code "51") (name "PPS") (class "Default")
      (node (ref "D5") (pin "A") (pinfunction "A_A") (pintype "passive"))
      (node (ref "J6") (pin "1") (pinfunction "1_1") (pintype "passive"))
      (node (ref "R12") (pin "2") (pinfunction "2_2") (pintype "passive"))
    )
    (net (code "52") (name "RF_IN") (class "Default")
      (node (ref "D9") (pin "2") (pinfunction "2_2") (pintype "bidirectional"))
      (node (ref "FB1") (pin "1") (pinfunction "1_1") (pintype "passive"))
      (node (ref "J1") (pin "FEED") (pinfunction "SIGNAL_FEED") (pintype "bidirectional"))
      (node (ref "U6") (pin "P2") (pinfunction "RF_IN_P2") (pintype "input"))
    )
    (net (code "53") (name "RTK_STAT") (class "Default")
      (node (ref "R11") (pin "P8") (pinfunction "2_P8") (pintype "passive"))
      (node (ref "RTK") (pin "1") (pinfunction "1_1") (pintype "passive"))
    )
    (net (code "54") (name "RXI2") (class "Default")
      (node (ref "J7") (pin "3") (pinfunction "3_3") (pintype "passive"))
      (node (ref "R10") (pin "P7") (pinfunction "2_P7") (pintype "passive"))
    )
    (net (code "55") (name "RXI{slash}POCI") (class "Default")
      (node (ref "J5") (pin "5") (pinfunction "5_5") (pintype "passive"))
      (node (ref "R9") (pin "P2") (pinfunction "1_P2") (pintype "passive"))
    )
    (net (code "56") (name "SCL{slash}CLK") (class "Default")
      (node (ref "J3") (pin "4") (pinfunction "4_4") (pintype "passive"))
      (node (ref "J4") (pin "4") (pinfunction "4_4") (pintype "passive"))
      (node (ref "J5") (pin "7") (pinfunction "7_7") (pintype "passive"))
      (node (ref "J6") (pin "6") (pinfunction "6_6") (pintype "passive"))
      (node (ref "R16") (pin "1") (pinfunction "1_1") (pintype "passive"))
      (node (ref "R9") (pin "P4") (pinfunction "1_P4") (pintype "passive"))
    )
    (net (code "57") (name "TXO2") (class "Default")
      (node (ref "J7") (pin "2") (pinfunction "2_2") (pintype "passive"))
      (node (ref "R10") (pin "P8") (pinfunction "2_P8") (pintype "passive"))
    )
    (net (code "58") (name "TXO{slash}PICO") (class "Default")
      (node (ref "J5") (pin "6") (pinfunction "6_6") (pintype "passive"))
      (node (ref "R9") (pin "P1") (pinfunction "1_P1") (pintype "passive"))
    )
    (net (code "59") (name "TX_READY") (class "Default")
      (node (ref "J6") (pin "5") (pinfunction "5_5") (pintype "passive"))
      (node (ref "R8") (pin "P1") (pinfunction "1_P1") (pintype "passive"))
    )
    (net (code "60") (name "VIN") (class "Default")
      (node (ref "C9") (pin "1") (pinfunction "1_1") (pintype "passive"))
      (node (ref "D3") (pin "5") (pinfunction "5_5") (pintype "power_in"))
      (node (ref "J2") (pin "VBUS1") (pinfunction "VBUS_VBUS1") (pintype "bidirectional"))
      (node (ref "J2") (pin "VBUS2") (pinfunction "VBUS_VBUS2") (pintype "bidirectional"))
      (node (ref "J5") (pin "2") (pinfunction "2_2") (pintype "passive"))
      (node (ref "U5") (pin "1") (pinfunction "IN_1") (pintype "input"))
      (node (ref "U5") (pin "3") (pinfunction "EN_3") (pintype "input"))
    )
    (net (code "61") (name "V_BATT") (class "Default")
      (node (ref "BT2") (pin "+") (pinfunction "+_+") (pintype "power_in"))
      (node (ref "C11") (pin "1") (pinfunction "1_1") (pintype "passive"))
      (node (ref "R24") (pin "1") (pinfunction "1_1") (pintype "passive"))
      (node (ref "TP1") (pin "1") (pinfunction "1_1") (pintype "bidirectional"))
      (node (ref "U6") (pin "P36") (pinfunction "V_BKCP_P36") (pintype "power_in"))
    )
    (net (code "62") (name "V_RF") (class "Default")
      (node (ref "R13") (pin "2") (pinfunction "2_2") (pintype "passive"))
      (node (ref "U6") (pin "P7") (pinfunction "V_RF_P7") (pintype "output"))
    )
    (net (code "63") (name "WT+") (class "Default")
      (node (ref "J5") (pin "11") (pinfunction "11_11") (pintype "passive"))
      (node (ref "R2") (pin "1") (pinfunction "1_1") (pintype "passive"))
    )
    (net (code "64") (name "WT_IN") (class "Default")
      (node (ref "R6") (pin "2") (pinfunction "2_2") (pintype "passive"))
      (node (ref "U1") (pin "1") (pinfunction "ANODE1_1") (pintype "input"))
    )
    (net (code "65") (name "WT_INV") (class "Default")
      (node (ref "R7") (pin "1") (pinfunction "1_1") (pintype "passive"))
      (node (ref "U1") (pin "7") (pinfunction "VOUT1_7") (pintype "output"))
      (node (ref "U3") (pin "P2") (pinfunction "A_P2") (pintype "input"))
    )
    (net (code "66") (name "WT_OUT") (class "Default")
      (node (ref "R10") (pin "P5") (pinfunction "2_P5") (pintype "passive"))
      (node (ref "U3") (pin "P4") (pinfunction "Y_P4") (pintype "output"))
    )
    (net (code "67") (name "unconnected-(J7-Pad1)") (class "Default")
      (node (ref "J7") (pin "1") (pinfunction "1_1") (pintype "passive"))
    )
    (net (code "68") (name "unconnected-(J7-Pad4)") (class "Default")
      (node (ref "J7") (pin "4") (pinfunction "4_4") (pintype "passive"))
    )
    (net (code "69") (name "unconnected-(J7-Pad5)") (class "Default")
      (node (ref "J7") (pin "5") (pinfunction "5_5") (pintype "passive"))
    )
    (net (code "70") (name "unconnected-(U6-ANT_DETECT-PadP4)") (class "Default")
      (node (ref "U6") (pin "P4") (pinfunction "ANT_DETECT_P4") (pintype "input"))
    )
    (net (code "71") (name "unconnected-(U6-ANT_OFF-PadP5)") (class "Default")
      (node (ref "U6") (pin "P5") (pinfunction "ANT_OFF_P5") (pintype "output"))
    )
    (net (code "72") (name "unconnected-(U6-~{ANT_SHORT}-PadP6)") (class "Default")
      (node (ref "U6") (pin "P6") (pinfunction "~{ANT_SHORT}_P6") (pintype "output"))
    )
  )
)
